# Copy_of_Gandhvedh_U_K.net
KiCad netlist of a schematic drawn in Altium Designer
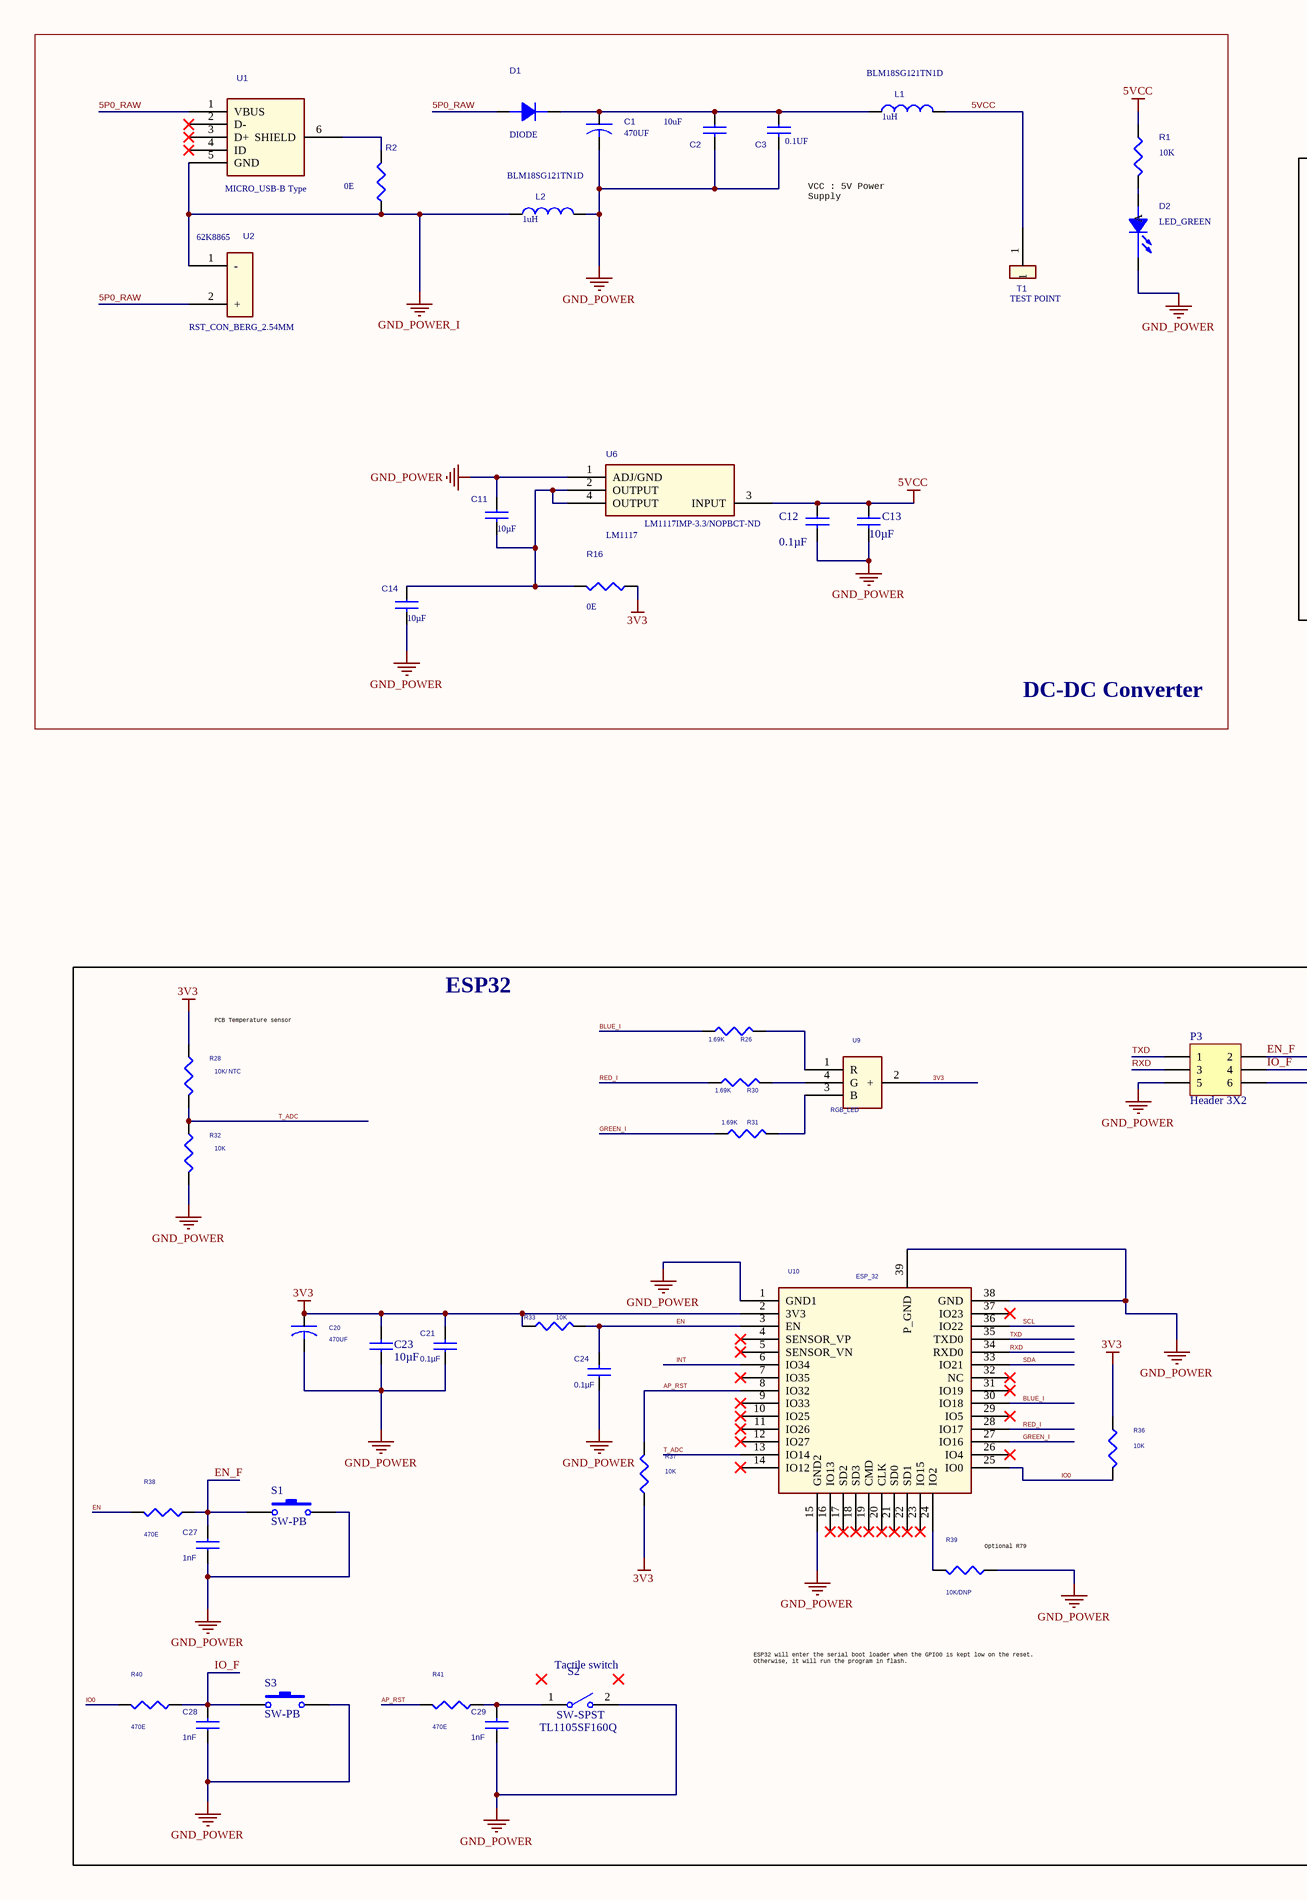
[diagram p0: Copy of Gandhvedh.U.K.SchDoc, left]
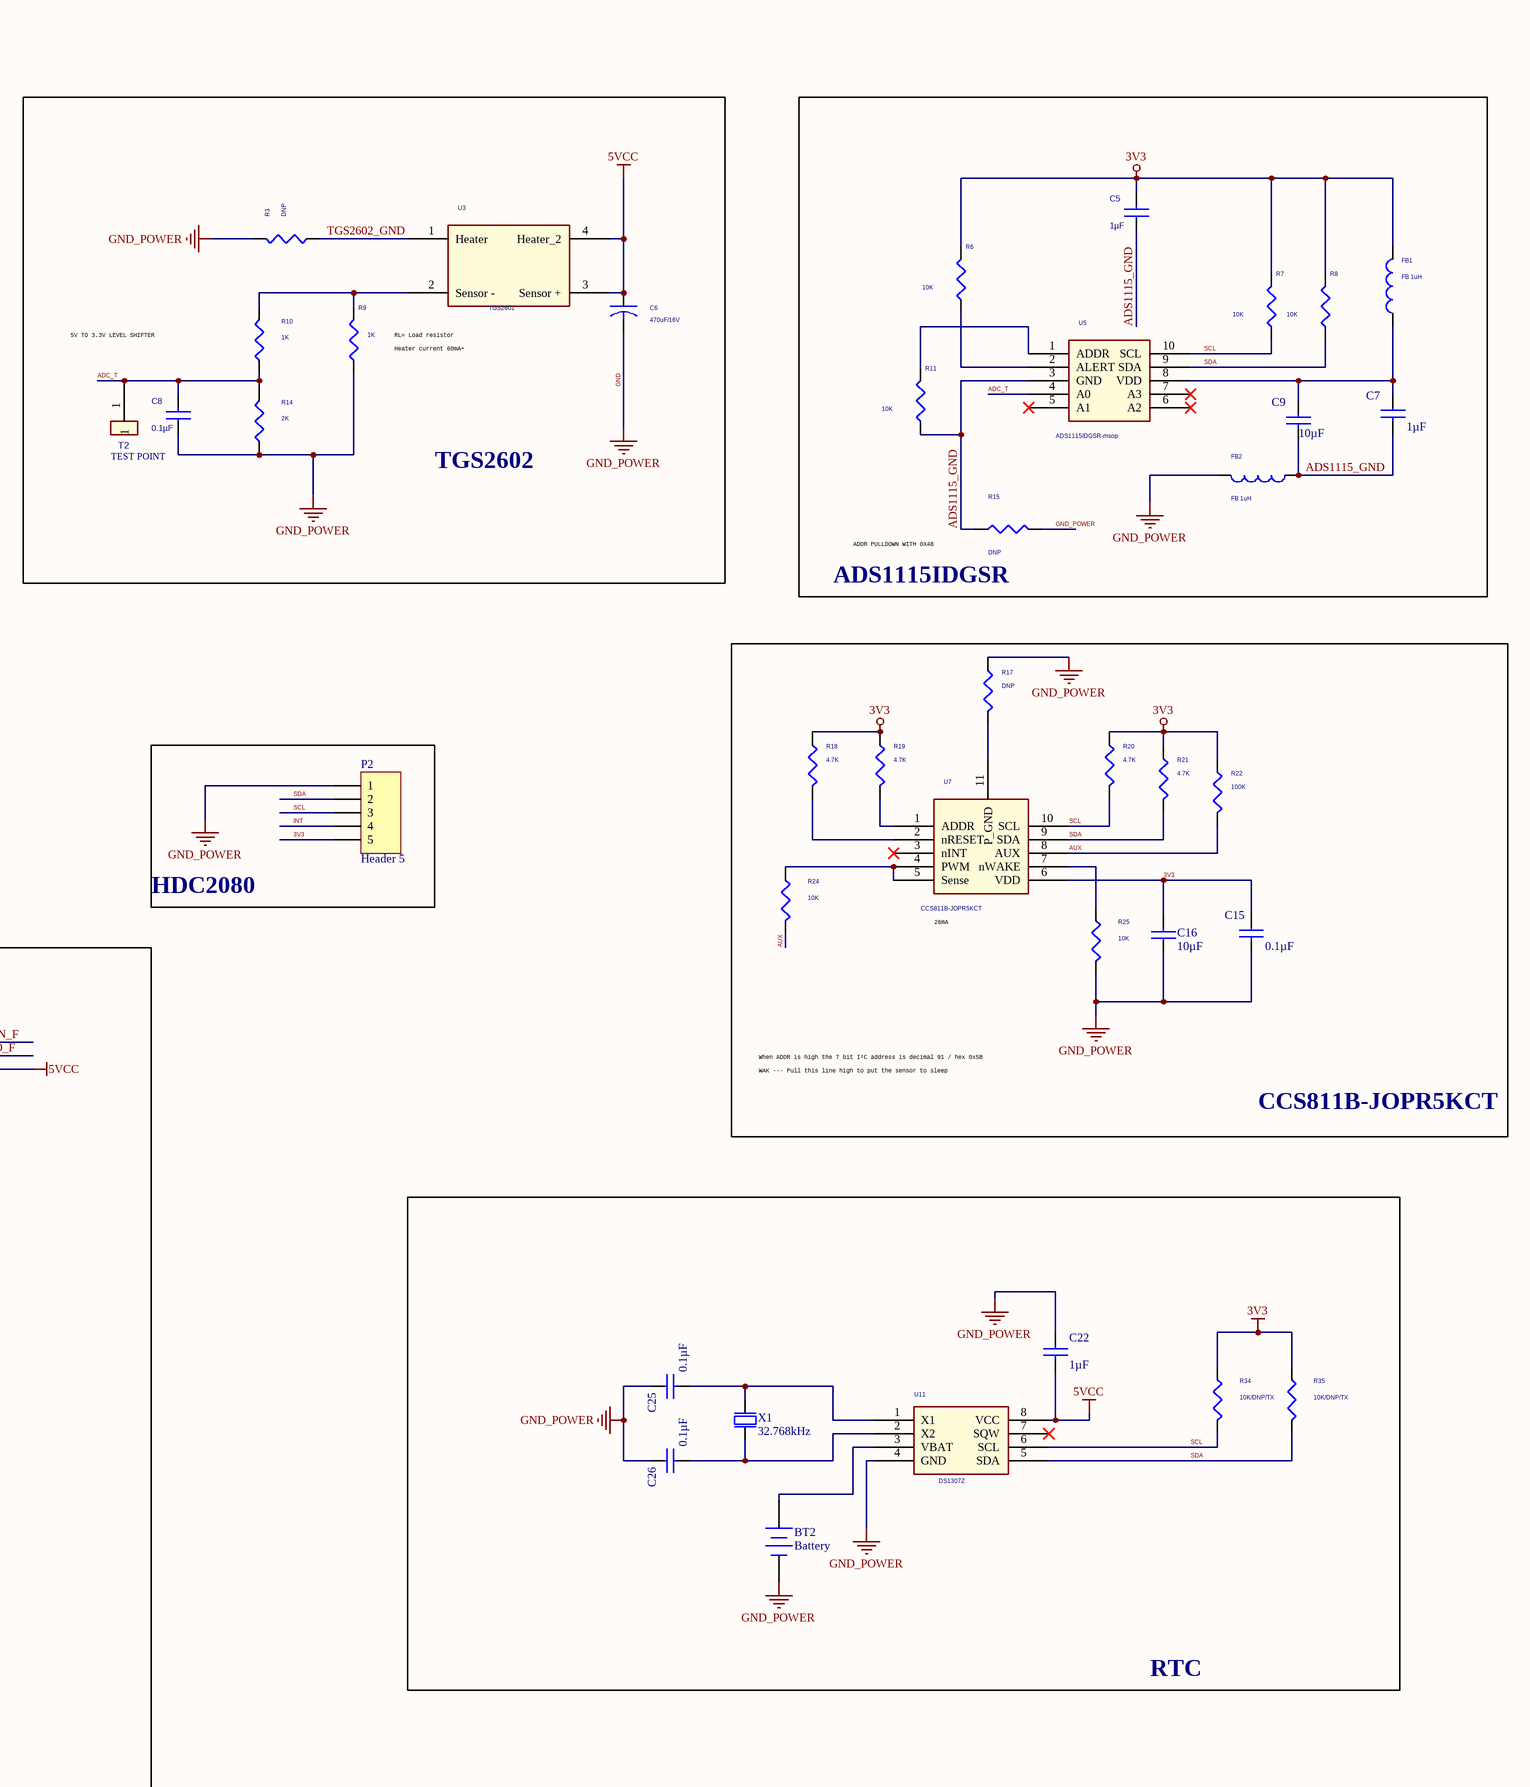
[diagram p1: Copy of Gandhvedh.U.K.SchDoc, middle]
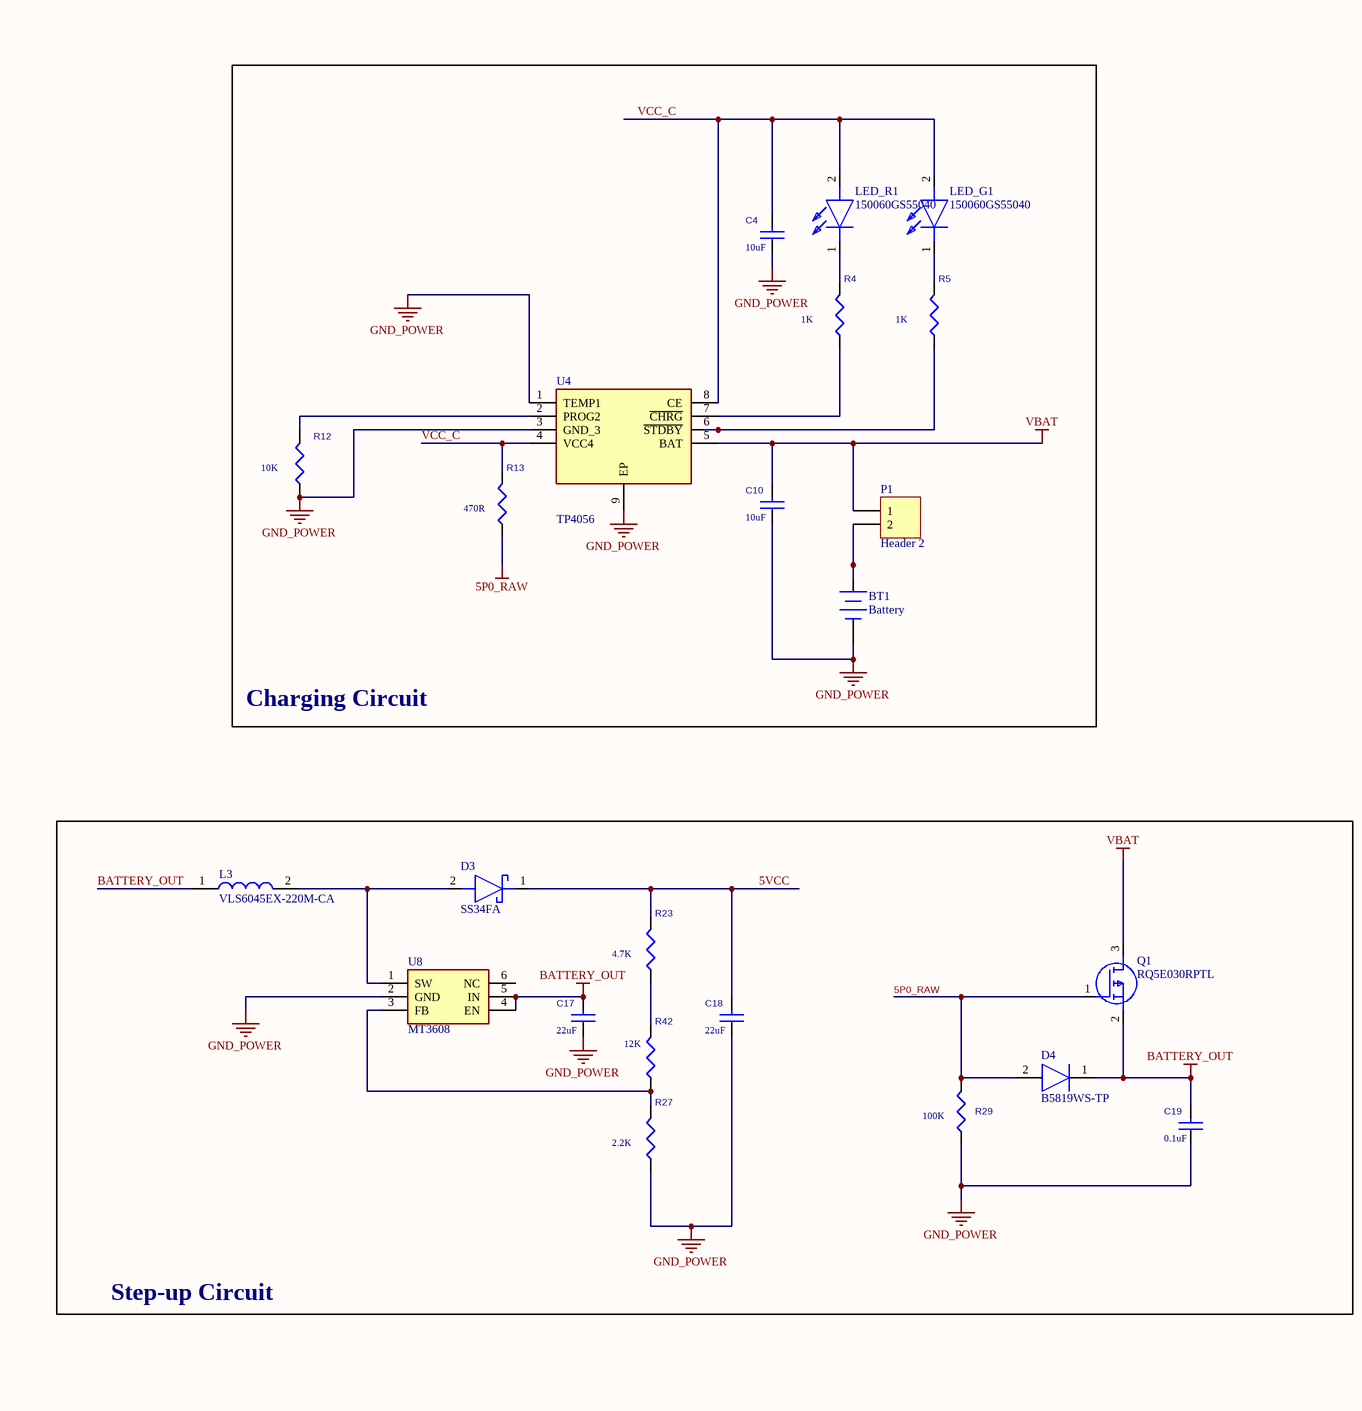
[diagram p2: Copy of Gandhvedh.U.K.SchDoc, right]

(export (version "E")
  (design (tool "Eeschema 10.0.6"))
  (components
    (comp (ref "BT1")
      (value "Battery")
      (footprint "BAT-2")
      (description "Multicell Battery")
      (fields (field (name "PUBLISHER") "Altium Limited"))
      (libsource (lib "Miscellaneous Devices") (part "Battery"))
    )
    (comp (ref "BT2")
      (value "Battery")
      (footprint "Sensor Card:MPD_BK-912-TR")
      (description "Multicell Battery")
      (fields (field (name "PUBLISHER") "Altium Limited"))
      (libsource (lib "Miscellaneous Devices") (part "Battery"))
    )
    (comp (ref "C1")
      (value "470UF")
      (footprint "C16, C49, C58")
      (description "CAP ALUM 470UF 20% 50V RADIAL")
      (fields (field (name "PART NUMBER") "871-B41896E6477M000"))
      (libsource (lib "*") (part "CAP"))
    )
    (comp (ref "C2")
      (value "10uF")
      (footprint "C0603")
      (description "CAP CER 22UF 10V X5R 0603")
      (fields (field (name "PART NUMBER") "GRM188R61A226ME15D"))
      (libsource (lib "*") (part "CAP NP"))
    )
    (comp (ref "C3")
      (value "0.1UF")
      (footprint "C0603")
      (description "CAP CER 22UF 10V X5R 0603")
      (fields (field (name "PART NUMBER") "GRM188R61A226ME15D"))
      (libsource (lib "*") (part "CAP NP"))
    )
    (comp (ref "C4")
      (value "10uF")
      (footprint "PCB1:C0603")
      (description "CAP CER SMD 0.1µF/16V")
      (fields
        (field (name "MANUFACTURER") "Murata Electronics North America")
        (field (name "MANUFACTURER PART NUMBER") "GRM155R61H104KE19D")
      )
      (libsource (lib "Passive Component") (part "CAP_C_0.1µF/16V"))
    )
    (comp (ref "C5")
      (value "1µF")
      (footprint "C0603")
      (description "CAP CER SMD 0.1µF/16V")
      (fields
        (field (name "MANUFACTURER") "Murata Electronics North America")
        (field (name "MANUFACTURER PART NUMBER") "GRM155R61H104KE19D")
      )
      (libsource (lib "Passive Component") (part "CAP_C_0.1µF/16V"))
    )
    (comp (ref "C6")
      (value "470uF/16V")
      (footprint "C16, C49, C58")
      (description "CAP ALUM 470UF 20% 50V RADIAL")
      (fields (field (name "PART NUMBER") "871-B41896E6477M000"))
      (libsource (lib "*") (part "CAP"))
    )
    (comp (ref "C7")
      (value "1µF")
      (footprint "C0603")
      (description "CAP CER SMD 0.1µF/50V")
      (fields
        (field (name "MANUFACTURER") "Yageo")
        (field (name "MANUFACTURER PART NUMBER") "CC0805ZRY5V9BB104")
      )
      (libsource (lib "Passive Component") (part "CAP_C_0.1µF/50V"))
    )
    (comp (ref "C8")
      (value "0.1µF")
      (footprint "C0603")
      (description "CAP CER SMD 0.1µF/16V")
      (fields
        (field (name "MANUFACTURER") "Murata Electronics North America")
        (field (name "MANUFACTURER PART NUMBER") "GRM155R61H104KE19D")
      )
      (libsource (lib "Passive Component") (part "CAP_C_0.1µF/16V"))
    )
    (comp (ref "C9")
      (value "10µF")
      (footprint "C0603")
      (description "CAP CER SMD 10µF/35V")
      (fields
        (field (name "MANUFACTURER") "Taiyo Yuden")
        (field (name "MANUFACTURER PART NUMBER") "GMK316AB7106KL-TR")
      )
      (libsource (lib "Passive Component") (part "CAP_C_10µF/35V"))
    )
    (comp (ref "C10")
      (value "10uF")
      (footprint "PCB1:C0603")
      (description "CAP CER SMD 0.1µF/16V")
      (fields
        (field (name "MANUFACTURER") "Murata Electronics North America")
        (field (name "MANUFACTURER PART NUMBER") "GRM155R61H104KE19D")
      )
      (libsource (lib "Passive Component") (part "CAP_C_0.1µF/16V"))
    )
    (comp (ref "C11")
      (value "10µF")
      (footprint "C0603")
      (description "CAP CER SMD 10µF/35V")
      (fields
        (field (name "MANUFACTURER") "Taiyo Yuden")
        (field (name "MANUFACTURER PART NUMBER") "GMK316AB7106KL-TR")
      )
      (libsource (lib "Passive Component") (part "CAP_C_10µF/35V"))
    )
    (comp (ref "C12")
      (value "0.1µF")
      (footprint "0603 Capacitor")
      (description "CAP CER SMD 0.1µF/50V")
      (fields
        (field (name "MANUFACTURER") "Yageo")
        (field (name "MANUFACTURER PART NUMBER") "CC0805ZRY5V9BB104")
      )
      (libsource (lib "Passive Component") (part "CAP_C_0.1µF/50V"))
    )
    (comp (ref "C13")
      (value "10µF")
      (footprint "0603 Capacitor")
      (description "CAP CER SMD 10µF/35V")
      (fields
        (field (name "MANUFACTURER") "Taiyo Yuden")
        (field (name "MANUFACTURER PART NUMBER") "GMK316AB7106KL-TR")
      )
      (libsource (lib "Passive Component") (part "CAP_C_10µF/35V"))
    )
    (comp (ref "C14")
      (value "10µF")
      (footprint "C0603")
      (description "CAP CER SMD 10µF/35V")
      (fields
        (field (name "MANUFACTURER") "Taiyo Yuden")
        (field (name "MANUFACTURER PART NUMBER") "GMK316AB7106KL-TR")
      )
      (libsource (lib "Passive Component") (part "CAP_C_10µF/35V"))
    )
    (comp (ref "C15")
      (value "0.1µF")
      (footprint "C0603")
      (description "CAP CER SMD 0.1µF/50V")
      (fields
        (field (name "MANUFACTURER") "Yageo")
        (field (name "MANUFACTURER PART NUMBER") "CC0805ZRY5V9BB104")
      )
      (libsource (lib "Passive Component") (part "CAP_C_0.1µF/50V"))
    )
    (comp (ref "C16")
      (value "10µF")
      (footprint "C0603")
      (description "CAP CER SMD 10µF/10V")
      (fields
        (field (name "MANUFACTURER") "Yageo")
        (field (name "MANUFACTURER PART NUMBER") "CC0805ZKY5V6BB106")
      )
      (libsource (lib "Passive Component") (part "CAP_C_10µF/10V"))
    )
    (comp (ref "C17")
      (value "22uF")
      (footprint "PCB1:C0603")
      (description "CAP CER SMD 0.1µF/16V")
      (fields
        (field (name "MANUFACTURER") "Murata Electronics North America")
        (field (name "MANUFACTURER PART NUMBER") "GRM155R61H104KE19D")
      )
      (libsource (lib "Passive Component") (part "CAP_C_0.1µF/16V"))
    )
    (comp (ref "C18")
      (value "22uF")
      (footprint "PCB1:C0603")
      (description "CAP CER SMD 0.1µF/16V")
      (fields
        (field (name "MANUFACTURER") "Murata Electronics North America")
        (field (name "MANUFACTURER PART NUMBER") "GRM155R61H104KE19D")
      )
      (libsource (lib "Passive Component") (part "CAP_C_0.1µF/16V"))
    )
    (comp (ref "C19")
      (value "0.1uF")
      (footprint "PCB1:C0603")
      (description "CAP CER SMD 0.1µF/16V")
      (fields
        (field (name "MANUFACTURER") "Murata Electronics North America")
        (field (name "MANUFACTURER PART NUMBER") "GRM155R61H104KE19D")
      )
      (libsource (lib "Passive Component") (part "CAP_C_0.1µF/16V"))
    )
    (comp (ref "C20")
      (value "470UF")
      (footprint "C16, C49, C58")
      (description "CAP ALUM 470UF 20% 50V RADIAL")
      (fields (field (name "PART NUMBER") "871-B41896E6477M000"))
      (libsource (lib "*") (part "CAP"))
    )
    (comp (ref "C21")
      (value "0.1µF")
      (footprint "0603 Capacitor")
      (description "CAP CER SMD 0.1µF/16V")
      (fields
        (field (name "MANUFACTURER") "Murata Electronics North America")
        (field (name "MANUFACTURER PART NUMBER") "GRM155R61H104KE19D")
      )
      (libsource (lib "Passive Component") (part "CAP_C_0.1µF/16V"))
    )
    (comp (ref "C22")
      (value "1µF")
      (footprint "C0603")
      (description "CAP CER SMD 0.1µF/50V")
      (fields
        (field (name "MANUFACTURER") "Yageo")
        (field (name "MANUFACTURER PART NUMBER") "CC0805ZRY5V9BB104")
      )
      (libsource (lib "Passive Component") (part "CAP_C_0.1µF/50V"))
    )
    (comp (ref "C23")
      (value "10µF")
      (footprint "C0603")
      (description "CAP CER SMD 10µF/10V")
      (fields
        (field (name "MANUFACTURER") "Yageo")
        (field (name "MANUFACTURER PART NUMBER") "CC0805ZKY5V6BB106")
      )
      (libsource (lib "Passive Component") (part "CAP_C_10µF/10V"))
    )
    (comp (ref "C24")
      (value "0.1µF")
      (footprint "C0603")
      (description "CAP CER SMD 0.1µF/16V")
      (fields
        (field (name "MANUFACTURER") "Murata Electronics North America")
        (field (name "MANUFACTURER PART NUMBER") "GRM155R61H104KE19D")
      )
      (libsource (lib "Passive Component") (part "CAP_C_0.1µF/16V"))
    )
    (comp (ref "C25")
      (value "0.1µF")
      (footprint "C0603")
      (description "CAP CER SMD 0.1µF/50V")
      (fields
        (field (name "MANUFACTURER") "Yageo")
        (field (name "MANUFACTURER PART NUMBER") "CC0805ZRY5V9BB104")
      )
      (libsource (lib "Passive Component") (part "CAP_C_0.1µF/50V"))
    )
    (comp (ref "C26")
      (value "0.1µF")
      (footprint "C0603")
      (description "CAP CER SMD 0.1µF/50V")
      (fields
        (field (name "MANUFACTURER") "Yageo")
        (field (name "MANUFACTURER PART NUMBER") "CC0805ZRY5V9BB104")
      )
      (libsource (lib "Passive Component") (part "CAP_C_0.1µF/50V"))
    )
    (comp (ref "C27")
      (value "1nF")
      (footprint "C0603")
      (description "CAP CER SMD 0.1µF/16V")
      (fields
        (field (name "MANUFACTURER") "Murata Electronics North America")
        (field (name "MANUFACTURER PART NUMBER") "GRM155R61H104KE19D")
      )
      (libsource (lib "Passive Component") (part "CAP_C_0.1µF/16V"))
    )
    (comp (ref "C28")
      (value "1nF")
      (footprint "C0603")
      (description "CAP CER SMD 0.1µF/16V")
      (fields
        (field (name "MANUFACTURER") "Murata Electronics North America")
        (field (name "MANUFACTURER PART NUMBER") "GRM155R61H104KE19D")
      )
      (libsource (lib "Passive Component") (part "CAP_C_0.1µF/16V"))
    )
    (comp (ref "C29")
      (value "1nF")
      (footprint "C0603")
      (description "CAP CER SMD 0.1µF/16V")
      (fields
        (field (name "MANUFACTURER") "Murata Electronics North America")
        (field (name "MANUFACTURER PART NUMBER") "GRM155R61H104KE19D")
      )
      (libsource (lib "Passive Component") (part "CAP_C_0.1µF/16V"))
    )
    (comp (ref "D1")
      (value "DIODE")
      (footprint "D1")
      (description "DIODE GEN PURP 1KV 1A DO214AC")
      (fields (field (name "PART NUMBER") "641-1018-2-ND"))
      (libsource (lib "*") (part "DIODE"))
    )
    (comp (ref "D2")
      (value "LED_GREEN")
      (footprint "D2              L0603")
      (description "LED GREEN CLEAR THIN 0603 SMD")
      (fields
        (field (name "DISTRIBUTOR PART NUMBER") "160-1443-1-ND")
        (field (name "MANUFACTURER PART NUMBER") "160-1443-2-ND")
      )
      (libsource (lib "*") (part "LED"))
    )
    (comp (ref "D3")
      (value "SS34FA")
      (footprint "PCB1:D1")
      (description "Schottky Diode")
      (fields (field (name "MOUSER PART NUMBER") "512-SS34FA"))
      (libsource (lib "*") (part "SS34FA"))
    )
    (comp (ref "D4")
      (value "B5819WS-TP")
      (footprint "PCB1:D1")
      (description "Diode")
      (fields (field (name "MOUSER PART NUMBER") "833-B5819WS-TP"))
      (libsource (lib "*") (part "B5819WS-TP"))
    )
    (comp (ref "FB1")
      (value "FB 1uH")
      (footprint "0603 Capacitor")
      (description "FILTER CHIP 120 OHM 3A 0603")
      (fields (field (name "MANUFACTURER PART NUMBER") "MMZ2012Y152B"))
      (libsource (lib "*") (part "INDUCTOR"))
    )
    (comp (ref "FB2")
      (value "FB 1uH")
      (footprint "0603 Capacitor")
      (description "FILTER CHIP 120 OHM 3A 0603")
      (fields (field (name "DISTRIBUTOR PART NUMBER") "MMZ2012Y152B"))
      (libsource (lib "*") (part "INDUCTOR"))
    )
    (comp (ref "L1")
      (value "1uH")
      (footprint "L3, L4, L5, L6, L7")
      (description "FERRITE BEAD 120 OHM 0603 1LN")
      (fields
        (field (name "PART NUMBER") "490-3996-1-ND")
        (field (name "SUPPLIER PART NUMBER 1") "BLM18SG121TN1D")
      )
      (libsource (lib "*") (part "INDUCTOR"))
    )
    (comp (ref "L2")
      (value "1uH")
      (footprint "L3, L4, L5, L6, L7")
      (description "FERRITE BEAD 120 OHM 0603 1LN")
      (fields
        (field (name "PART NUMBER") "490-3996-1-ND")
        (field (name "SUPPLIER PART NUMBER 1") "BLM18SG121TN1D")
      )
      (libsource (lib "*") (part "INDUCTOR"))
    )
    (comp (ref "L3")
      (value "VLS6045EX-220M-CA")
      (footprint "SamacSys:VLS6045")
      (description "Inductor")
      (fields (field (name "MOUSER PART NUMBER") "810-VLS6045EX220MCA"))
      (libsource (lib "*") (part "VLS6045EX-220M-CA"))
    )
    (comp (ref "LED_G1")
      (value "150060GS55040")
      (footprint "SamacSys:LEDC1608X50N")
      (description "LED")
      (fields (field (name "MOUSER PART NUMBER") "710-150060GS55040"))
      (libsource (lib "*") (part "150060GS55040"))
    )
    (comp (ref "LED_R1")
      (value "150060GS55040")
      (footprint "SamacSys:LEDC1608X50N")
      (description "LED")
      (fields (field (name "MOUSER PART NUMBER") "710-150060GS55040"))
      (libsource (lib "*") (part "150060GS55040"))
    )
    (comp (ref "P1")
      (value "Header 2")
      (footprint "Miscellaneous Connectors:HDR1X2")
      (description "Header, 2-Pin")
      (fields (field (name "PUBLISHER") "Altium Limited"))
      (libsource (lib "Miscellaneous Connectors") (part "Header 2"))
    )
    (comp (ref "P2")
      (value "Header 5")
      (footprint "HDR1X5")
      (description "Header, 5-Pin")
      (fields (field (name "PUBLISHER") "Altium Limited"))
      (libsource (lib "Miscellaneous Connectors") (part "Header 5"))
    )
    (comp (ref "P3")
      (value "Header 3X2")
      (footprint "HDR2X3")
      (description "Header, 3-Pin, Dual row")
      (fields (field (name "PUBLISHER") "Altium Limited"))
      (libsource (lib "Miscellaneous Connectors") (part "Header 3X2"))
    )
    (comp (ref "Q1")
      (value "RQ5E030RPTL")
      (footprint "SamacSys:SOT95P280X100-3N")
      (description "MOSFET (P-Channel)")
      (fields (field (name "MOUSER PART NUMBER") "755-RQ5E030RPTL"))
      (libsource (lib "*") (part "RQ5E030RPTL"))
    )
    (comp (ref "R1")
      (value "10K")
      (footprint "R0603")
      (description "RES SMD 1K OHM 5% 1/10W 0603")
      (fields (field (name "PART NUMBER") "311-1.0KGRTR-ND"))
      (libsource (lib "*") (part "R"))
    )
    (comp (ref "R2")
      (value "0E")
      (footprint "R0603")
      (description "RES SMD 4.7K OHM 1% 1/16W 0603")
      (fields (field (name "TOLERANCE") "1%") (field (name "DISTRIBUTOR PART NUMBER") "1276-3466-2-ND"))
      (libsource (lib "*") (part "R"))
    )
    (comp (ref "R3") (value "DNP") (footprint "R0603") (libsource (lib "*") (part "R")))
    (comp (ref "R4")
      (value "1K")
      (footprint "PCB1:R0603")
      (description "RES SMD 4.7K OHM 1% 1/16W 0603")
      (fields (field (name "TOLERANCE") "1%") (field (name "DISTRIBUTOR PART NUMBER") "1276-3466-2-ND"))
      (libsource (lib "*") (part "R"))
    )
    (comp (ref "R5")
      (value "1K")
      (footprint "PCB1:R0603")
      (description "RES SMD 4.7K OHM 1% 1/16W 0603")
      (fields (field (name "TOLERANCE") "1%") (field (name "DISTRIBUTOR PART NUMBER") "1276-3466-2-ND"))
      (libsource (lib "*") (part "R"))
    )
    (comp (ref "R6")
      (value "10K")
      (footprint "R0603")
      (description "RES SMD 4.7K OHM 1% 1/16W 0603")
      (fields (field (name "TOLERANCE") "1%") (field (name "DISTRIBUTOR PART NUMBER") "1276-3466-2-ND"))
      (libsource (lib "*") (part "R"))
    )
    (comp (ref "R7")
      (value "10K")
      (footprint "R0603")
      (description "RES SMD 4.7K OHM 1% 1/16W 0603")
      (fields (field (name "TOLERANCE") "1%") (field (name "DISTRIBUTOR PART NUMBER") "1276-3466-2-ND"))
      (libsource (lib "*") (part "R"))
    )
    (comp (ref "R8")
      (value "10K")
      (footprint "R0603")
      (description "RES SMD 4.7K OHM 1% 1/16W 0603")
      (fields (field (name "TOLERANCE") "1%") (field (name "DISTRIBUTOR PART NUMBER") "1276-3466-2-ND"))
      (libsource (lib "*") (part "R"))
    )
    (comp (ref "R9")
      (value "1K")
      (footprint "R0603")
      (description "RES SMD 1K OHM 5% 1/10W 0603")
      (fields (field (name "PART NUMBER") "311-1.0KGRTR-ND") (field (name "TOLERANCE") "1%"))
      (libsource (lib "*") (part "R"))
    )
    (comp (ref "R10")
      (value "1K")
      (footprint "R0603")
      (description "RES SMD 1K OHM 5% 1/10W 0603")
      (fields (field (name "PART NUMBER") "311-1.0KGRTR-ND"))
      (libsource (lib "*") (part "R"))
    )
    (comp (ref "R11")
      (value "10K")
      (footprint "R0603")
      (description "RES SMD 4.7K OHM 1% 1/16W 0603")
      (fields (field (name "TOLERANCE") "1%") (field (name "DISTRIBUTOR PART NUMBER") "1276-3466-2-ND"))
      (libsource (lib "*") (part "R"))
    )
    (comp (ref "R12")
      (value "10K")
      (footprint "PCB1:R0603")
      (description "RES SMD 4.7K OHM 1% 1/16W 0603")
      (fields (field (name "TOLERANCE") "1%") (field (name "DISTRIBUTOR PART NUMBER") "1276-3466-2-ND"))
      (libsource (lib "*") (part "R"))
    )
    (comp (ref "R13")
      (value "470R")
      (footprint "PCB1:R0603")
      (description "RES SMD 4.7K OHM 1% 1/16W 0603")
      (fields (field (name "TOLERANCE") "1%") (field (name "DISTRIBUTOR PART NUMBER") "1276-3466-2-ND"))
      (libsource (lib "*") (part "R"))
    )
    (comp (ref "R14")
      (value "2K")
      (footprint "R0603")
      (description "RES SMD 2K OHM 1% 1/10W 0603")
      (fields (field (name "PART NUMBER") "YAG1297CT-ND"))
      (libsource (lib "*") (part "R"))
    )
    (comp (ref "R15") (value "DNP") (footprint "R0603") (libsource (lib "*") (part "R")))
    (comp (ref "R16")
      (value "0E")
      (footprint "R0603")
      (description "RES SMD 470 OHM 1% 1/10W 0603")
      (fields (field (name "PART NUMBER") "311-470HRCT-ND"))
      (libsource (lib "*") (part "R"))
    )
    (comp (ref "R17") (value "DNP") (footprint "R0603") (libsource (lib "*") (part "R")))
    (comp (ref "R18")
      (value "4.7K")
      (footprint "R0603")
      (description "P4.7KDBTR-ND")
      (fields (field (name "PART NUMBER") "P4.7KDBDKR-ND"))
      (libsource (lib "*") (part "R"))
    )
    (comp (ref "R19")
      (value "4.7K")
      (footprint "R0603")
      (description "P4.7KDBTR-ND")
      (fields (field (name "PART NUMBER") "P4.7KDBDKR-ND"))
      (libsource (lib "*") (part "R"))
    )
    (comp (ref "R20")
      (value "4.7K")
      (footprint "R0603")
      (description "P4.7KDBTR-ND")
      (fields (field (name "PART NUMBER") "P4.7KDBDKR-ND"))
      (libsource (lib "*") (part "R"))
    )
    (comp (ref "R21")
      (value "4.7K")
      (footprint "R0603")
      (description "P4.7KDBTR-ND")
      (fields (field (name "PART NUMBER") "P4.7KDBDKR-ND"))
      (libsource (lib "*") (part "R"))
    )
    (comp (ref "R22")
      (value "100K")
      (footprint "R0603")
      (description "RES SMD 100K OHM 0.1% 1/10W 0603")
      (fields (field (name "PART NUMBER") "YAG1235TR-ND"))
      (libsource (lib "*") (part "R"))
    )
    (comp (ref "R23")
      (value "4.7K")
      (footprint "PCB1:R0603")
      (description "RES SMD 4.7K OHM 1% 1/16W 0603")
      (fields (field (name "TOLERANCE") "1%") (field (name "DISTRIBUTOR PART NUMBER") "1276-3466-2-ND"))
      (libsource (lib "*") (part "R"))
    )
    (comp (ref "R24")
      (value "10K")
      (footprint "R0603")
      (fields (field (name "PART NUMBER") "594-NTCS402E3103JL1T"))
      (libsource (lib "*") (part "R"))
    )
    (comp (ref "R25")
      (value "10K")
      (footprint "R0603")
      (description "RES SMD 4.7K OHM 1% 1/16W 0603")
      (fields (field (name "PART NUMBER") "311-10KGRTR-ND"))
      (libsource (lib "*") (part "R"))
    )
    (comp (ref "R26")
      (value "1.69K")
      (footprint "R0603")
      (description "RES SMD 4.7K OHM 1% 1/16W 0603")
      (fields (field (name "PART NUMBER") "311-10KGRTR-ND"))
      (libsource (lib "*") (part "R"))
    )
    (comp (ref "R27")
      (value "2.2K")
      (footprint "PCB1:R0603")
      (description "RES SMD 4.7K OHM 1% 1/16W 0603")
      (fields (field (name "TOLERANCE") "1%") (field (name "DISTRIBUTOR PART NUMBER") "1276-3466-2-ND"))
      (libsource (lib "*") (part "R"))
    )
    (comp (ref "R28")
      (value "10K/ NTC")
      (footprint "R0603")
      (description "THERMISTOR NTC 10KOHM 3380K 0603")
      (fields (field (name "PART NUMBER") "490-16279-2-ND"))
      (libsource (lib "*") (part "R"))
    )
    (comp (ref "R29")
      (value "100K")
      (footprint "PCB1:R0603")
      (description "RES SMD 4.7K OHM 1% 1/16W 0603")
      (fields (field (name "TOLERANCE") "1%") (field (name "DISTRIBUTOR PART NUMBER") "1276-3466-2-ND"))
      (libsource (lib "*") (part "R"))
    )
    (comp (ref "R30")
      (value "1.69K")
      (footprint "R0603")
      (description "RES SMD 4.7K OHM 1% 1/16W 0603")
      (fields (field (name "PART NUMBER") "311-10KGRTR-ND"))
      (libsource (lib "*") (part "R"))
    )
    (comp (ref "R31")
      (value "1.69K")
      (footprint "R0603")
      (description "RES SMD 4.7K OHM 1% 1/16W 0603")
      (fields (field (name "PART NUMBER") "311-10KGRTR-ND"))
      (libsource (lib "*") (part "R"))
    )
    (comp (ref "R32")
      (value "10K")
      (footprint "R0603")
      (description "RES SMD 4.7K OHM 1% 1/16W 0603")
      (fields (field (name "PART NUMBER") "311-10KGRTR-ND"))
      (libsource (lib "*") (part "R"))
    )
    (comp (ref "R33")
      (value "10K")
      (footprint "R_0603_W")
      (description "RES SMD 4.7K OHM 1% 1/16W 0603")
      (fields (field (name "PART NUMBER") "311-10KGRTR-ND"))
      (libsource (lib "*") (part "R"))
    )
    (comp (ref "R34")
      (value "10K/DNP/TX")
      (footprint "R0603")
      (description "RES SMD 4.7K OHM 1% 1/16W 0603")
      (fields (field (name "PART NUMBER") "311-10KGRTR-ND"))
      (libsource (lib "*") (part "R"))
    )
    (comp (ref "R35")
      (value "10K/DNP/TX")
      (footprint "R0603")
      (description "RES SMD 4.7K OHM 1% 1/16W 0603")
      (fields (field (name "PART NUMBER") "311-10KGRTR-ND"))
      (libsource (lib "*") (part "R"))
    )
    (comp (ref "R36")
      (value "10K")
      (footprint "R0603")
      (description "RES SMD 4.7K OHM 1% 1/16W 0603")
      (fields (field (name "PART NUMBER") "311-10KGRTR-ND"))
      (libsource (lib "*") (part "R"))
    )
    (comp (ref "R37")
      (value "10K")
      (footprint "R0603")
      (description "RES SMD 4.7K OHM 1% 1/16W 0603")
      (fields (field (name "PART NUMBER") "311-10KGRTR-ND"))
      (libsource (lib "*") (part "R"))
    )
    (comp (ref "R38")
      (value "470E")
      (footprint "R0603")
      (description "RES SMD 470 OHM 1% 1/10W 0603")
      (fields (field (name "PART NUMBER") "311-470HRCT-ND"))
      (libsource (lib "*") (part "R"))
    )
    (comp (ref "R39")
      (value "10K/DNP")
      (footprint "R0603")
      (description "RES SMD 4.7K OHM 1% 1/16W 0603")
      (fields (field (name "PART NUMBER") "311-10KGRTR-ND"))
      (libsource (lib "*") (part "R"))
    )
    (comp (ref "R40")
      (value "470E")
      (footprint "R0603")
      (description "RES SMD 470 OHM 1% 1/10W 0603")
      (fields (field (name "PART NUMBER") "311-470HRCT-ND"))
      (libsource (lib "*") (part "R"))
    )
    (comp (ref "R41")
      (value "470E")
      (footprint "R0603")
      (description "RES SMD 470 OHM 1% 1/10W 0603")
      (fields (field (name "PART NUMBER") "311-470HRCT-ND"))
      (libsource (lib "*") (part "R"))
    )
    (comp (ref "R42")
      (value "12K")
      (footprint "PCB1:R0603")
      (description "RES SMD 4.7K OHM 1% 1/16W 0603")
      (fields (field (name "TOLERANCE") "1%") (field (name "DISTRIBUTOR PART NUMBER") "1276-3466-2-ND"))
      (libsource (lib "*") (part "R"))
    )
    (comp (ref "S1")
      (value "SW-PB")
      (footprint "S2, S3")
      (description "Switch")
      (fields (field (name "PUBLISHER") "Altium Limited"))
      (libsource (lib "Miscellaneous Devices") (part "SW-PB"))
    )
    (comp (ref "S2")
      (value "SW-SPST")
      (footprint "S1")
      (description "SWITCH TACTILE SPST-NO 0.05A 12V")
      (fields (field (name "PART NUMBER") "TL1105SF160Q") (field (name "PUBLISHER") "Altium Limited"))
      (libsource (lib "Miscellaneous Devices") (part "SW-SPST"))
    )
    (comp (ref "S3")
      (value "SW-PB")
      (footprint "S2, S3")
      (description "Switch")
      (fields (field (name "PUBLISHER") "Altium Limited"))
      (libsource (lib "Miscellaneous Devices") (part "SW-PB"))
    )
    (comp (ref "T1") (value "TEST POINT") (footprint "TP") (libsource (lib "*") (part "Test_P")))
    (comp (ref "T2") (value "TEST POINT") (footprint "TP") (libsource (lib "*") (part "Test_P")))
    (comp (ref "U1")
      (value "MICRO_USB-B Type")
      (footprint "U22")
      (description "CONN RCPT USB2.0 MICRO B SMD R/A")
      (libsource (lib "*") (part "MIcro_USB"))
    )
    (comp (ref "U2")
      (value "RST_CON_BERG_2.54MM")
      (footprint "U23")
      (description "CONN HEADER VERT 2POS 2.54MM")
      (fields (field (name "PART NUMBER") "609-4434-ND") (field (name "SUPPLIER PART NUMBER 1") "62K8865"))
      (libsource (lib "*") (part "CON_AC_1"))
    )
    (comp (ref "U3") (value "TGS2602") (footprint "TGS2602") (libsource (lib "*") (part "TGS2602_1")))
    (comp (ref "U4")
      (value "TP4056")
      (footprint "SamacSys:SOIC127P600X175-9N")
      (description "Connector")
      (libsource (lib "*") (part "TP4056"))
    )
    (comp (ref "U5")
      (value "ADS1115IDGSR-msop")
      (footprint "U19, U20")
      (description "IC ADC 16BIT SIGMA-DELTA 10VSSOP")
      (fields (field (name "PART NUMBER") "595-ADS1115IDGST"))
      (libsource (lib "*") (part "ADS1115"))
    )
    (comp (ref "U6")
      (value "LM1117")
      (footprint "U1, U24              SOT-223")
      (description "3.3V LDO")
      (fields
        (field (name "MANUFACTURER") "Texas Instruments")
        (field (name "SUPPLIER PART NUMBER 1") "LM1117IMP-3.3/NOPBCT-ND")
      )
      (libsource (lib "PMIC") (part "TLV70033DDCT"))
    )
    (comp (ref "U7")
      (value "CCS811B-JOPR5KCT")
      (footprint "*SON60P400X270X110-11N")
      (description "CCS811B-JOPR5K LGA10 LF T&R")
      (fields (field (name "PART NUMBER") "CCS811B-JOPR5KCT-ND"))
      (libsource (lib "*") (part "CCS811B-JOPR5KCT_3"))
    )
    (comp (ref "U8")
      (value "MT3608")
      (footprint "SamacSys:SOT95P280X145-6N")
      (description "Undefined or Miscellaneous")
      (libsource (lib "*") (part "MT3608"))
    )
    (comp (ref "U9")
      (value "RGB_LED")
      (footprint "Sensor Card:WL-SFCW_1206")
      (fields (field (name "PART NUMBER") "754-1492-ND"))
      (libsource (lib "*") (part "RGB_LED_PTH_0"))
    )
    (comp (ref "U10")
      (value "ESP_32")
      (footprint "U20             ESP 32")
      (description "WIFI MODULE 128MBITS SPI FLASH")
      (fields (field (name "PART NUMBER") "356-ES32WROOM32D16MB"))
      (libsource (lib "*") (part "ESP32_SMD_1"))
    )
    (comp (ref "U11")
      (value "DS1307Z")
      (footprint "U6, U8                    SOIC-8N")
      (description "IC REG BUCK ADJUSTABLE 3A 8SOIC")
      (fields (field (name "PART NUMBER") "1589-1533-1-ND"))
      (libsource (lib "*") (part "MP1584_SOIC_0"))
    )
    (comp (ref "X1")
      (value "32.768kHz")
      (footprint "XTAL")
      (description "XTAL SMD 3215, 32.768kHz, Cl=9pF, Total Tol: ±50ppm")
      (fields
        (field (name "PART NUMBER") "XTAL_SMD3215_32.768kHz_9pF_General")
        (field (name "PUBLISHER") "Nordic Semiconductor")
      )
      (libsource (lib "Sensor Card") (part "XTAL_2-pin"))
    )
  )
  (nets
    (net (code "1") (name "/ADC_T") (class "Default")
      (node (ref "C8") (pin "2") (pinfunction "2_2") (pintype "passive"))
      (node (ref "R10") (pin "1") (pinfunction "1_1") (pintype "passive"))
      (node (ref "R14") (pin "2") (pinfunction "2_2") (pintype "passive"))
      (node (ref "T2") (pin "1") (pinfunction "1_1") (pintype "passive"))
      (node (ref "U5") (pin "4") (pinfunction "A0_4") (pintype "passive"))
    )
    (net (code "2") (name "/ADS1115_GND") (class "Default")
      (node (ref "C5") (pin "1") (pinfunction "1_1") (pintype "passive"))
      (node (ref "C7") (pin "2") (pinfunction "2_2") (pintype "passive"))
      (node (ref "C9") (pin "2") (pinfunction "2_2") (pintype "passive"))
      (node (ref "FB2") (pin "1") (pinfunction "1_1") (pintype "passive"))
      (node (ref "R11") (pin "2") (pinfunction "2_2") (pintype "passive"))
      (node (ref "R15") (pin "1") (pinfunction "1_1") (pintype "passive"))
      (node (ref "U5") (pin "3") (pinfunction "GND_3") (pintype "passive"))
    )
    (net (code "3") (name "/AP_RST") (class "Default")
      (node (ref "R37") (pin "2") (pinfunction "2_2") (pintype "passive"))
      (node (ref "R41") (pin "2") (pinfunction "2_2") (pintype "passive"))
      (node (ref "U10") (pin "8") (pinfunction "IO32_8") (pintype "passive"))
    )
    (net (code "4") (name "/AUX") (class "Default")
      (node (ref "R22") (pin "2") (pinfunction "2_2") (pintype "passive"))
      (node (ref "R24") (pin "2") (pinfunction "2_2") (pintype "passive"))
      (node (ref "U7") (pin "8") (pinfunction "AUX_8") (pintype "passive"))
    )
    (net (code "5") (name "/BLUE_I") (class "Default")
      (node (ref "R26") (pin "1") (pinfunction "1_1") (pintype "passive"))
      (node (ref "U10") (pin "30") (pinfunction "IO18_30") (pintype "passive"))
    )
    (net (code "6") (name "/EN") (class "Default")
      (node (ref "C24") (pin "2") (pinfunction "2_2") (pintype "passive"))
      (node (ref "R33") (pin "2") (pinfunction "2_2") (pintype "passive"))
      (node (ref "R38") (pin "2") (pinfunction "2_2") (pintype "passive"))
      (node (ref "U10") (pin "3") (pinfunction "EN_3") (pintype "passive"))
    )
    (net (code "7") (name "/EN_F") (class "Default")
      (node (ref "C27") (pin "2") (pinfunction "2_2") (pintype "passive"))
      (node (ref "P3") (pin "2") (pinfunction "2_2") (pintype "passive"))
      (node (ref "R38") (pin "1") (pinfunction "1_1") (pintype "passive"))
      (node (ref "S1") (pin "1") (pinfunction "1_1") (pintype "passive"))
    )
    (net (code "8") (name "/GREEN_I") (class "Default")
      (node (ref "R31") (pin "1") (pinfunction "1_1") (pintype "passive"))
      (node (ref "U10") (pin "27") (pinfunction "IO16_27") (pintype "passive"))
    )
    (net (code "9") (name "/INT") (class "Default")
      (node (ref "P2") (pin "4") (pinfunction "4_4") (pintype "passive"))
      (node (ref "U10") (pin "6") (pinfunction "IO34_6") (pintype "passive"))
    )
    (net (code "10") (name "/IO0") (class "Default")
      (node (ref "R36") (pin "2") (pinfunction "2_2") (pintype "passive"))
      (node (ref "R40") (pin "2") (pinfunction "2_2") (pintype "passive"))
      (node (ref "U10") (pin "25") (pinfunction "IO0_25") (pintype "passive"))
    )
    (net (code "11") (name "/IO_F") (class "Default")
      (node (ref "C28") (pin "2") (pinfunction "2_2") (pintype "passive"))
      (node (ref "P3") (pin "4") (pinfunction "4_4") (pintype "passive"))
      (node (ref "R40") (pin "1") (pinfunction "1_1") (pintype "passive"))
      (node (ref "S3") (pin "1") (pinfunction "1_1") (pintype "passive"))
    )
    (net (code "12") (name "/RED_I") (class "Default")
      (node (ref "R30") (pin "1") (pinfunction "1_1") (pintype "passive"))
      (node (ref "U10") (pin "28") (pinfunction "IO17_28") (pintype "passive"))
    )
    (net (code "13") (name "/RXD") (class "Default")
      (node (ref "P3") (pin "3") (pinfunction "3_3") (pintype "passive"))
      (node (ref "U10") (pin "34") (pinfunction "RXD0_34") (pintype "passive"))
    )
    (net (code "14") (name "/SCL") (class "Default")
      (node (ref "P2") (pin "3") (pinfunction "3_3") (pintype "passive"))
      (node (ref "R20") (pin "2") (pinfunction "2_2") (pintype "passive"))
      (node (ref "R34") (pin "2") (pinfunction "2_2") (pintype "passive"))
      (node (ref "R7") (pin "2") (pinfunction "2_2") (pintype "passive"))
      (node (ref "U10") (pin "36") (pinfunction "IO22_36") (pintype "passive"))
      (node (ref "U11") (pin "6") (pinfunction "SCL_6") (pintype "passive"))
      (node (ref "U5") (pin "10") (pinfunction "SCL_10") (pintype "passive"))
      (node (ref "U7") (pin "10") (pinfunction "SCL_10") (pintype "passive"))
    )
    (net (code "15") (name "/SDA") (class "Default")
      (node (ref "P2") (pin "2") (pinfunction "2_2") (pintype "passive"))
      (node (ref "R21") (pin "2") (pinfunction "2_2") (pintype "passive"))
      (node (ref "R35") (pin "2") (pinfunction "2_2") (pintype "passive"))
      (node (ref "R8") (pin "2") (pinfunction "2_2") (pintype "passive"))
      (node (ref "U10") (pin "33") (pinfunction "IO21_33") (pintype "passive"))
      (node (ref "U11") (pin "5") (pinfunction "SDA_5") (pintype "passive"))
      (node (ref "U5") (pin "9") (pinfunction "SDA_9") (pintype "passive"))
      (node (ref "U7") (pin "9") (pinfunction "SDA_9") (pintype "passive"))
    )
    (net (code "16") (name "/TGS2602_GND") (class "Default")
      (node (ref "R3") (pin "1") (pinfunction "1_1") (pintype "passive"))
      (node (ref "U3") (pin "1") (pinfunction "Heater_1") (pintype "passive"))
    )
    (net (code "17") (name "/TXD") (class "Default")
      (node (ref "P3") (pin "1") (pinfunction "1_1") (pintype "passive"))
      (node (ref "U10") (pin "35") (pinfunction "TXD0_35") (pintype "passive"))
    )
    (net (code "18") (name "/T_ADC") (class "Default")
      (node (ref "R28") (pin "2") (pinfunction "2_2") (pintype "passive"))
      (node (ref "R32") (pin "1") (pinfunction "1_1") (pintype "passive"))
      (node (ref "U10") (pin "13") (pinfunction "IO14_13") (pintype "passive"))
    )
    (net (code "19") (name "/VCC_C") (class "Default")
      (node (ref "C4") (pin "2") (pinfunction "2_2") (pintype "passive"))
      (node (ref "LED_G1") (pin "2") (pinfunction "A_2") (pintype "passive"))
      (node (ref "LED_R1") (pin "2") (pinfunction "A_2") (pintype "passive"))
      (node (ref "R13") (pin "1") (pinfunction "1_1") (pintype "passive"))
      (node (ref "U4") (pin "4") (pinfunction "VCC4_4") (pintype "passive"))
      (node (ref "U4") (pin "8") (pinfunction "CE_8") (pintype "passive"))
    )
    (net (code "20") (name "3V3") (class "Default")
      (node (ref "C15") (pin "1") (pinfunction "1_1") (pintype "passive"))
      (node (ref "C16") (pin "2") (pinfunction "2_2") (pintype "passive"))
      (node (ref "C20") (pin "1") (pinfunction "1_1") (pintype "passive"))
      (node (ref "C21") (pin "2") (pinfunction "2_2") (pintype "passive"))
      (node (ref "C23") (pin "2") (pinfunction "2_2") (pintype "passive"))
      (node (ref "C5") (pin "2") (pinfunction "2_2") (pintype "passive"))
      (node (ref "FB1") (pin "2") (pinfunction "2_2") (pintype "passive"))
      (node (ref "P2") (pin "5") (pinfunction "5_5") (pintype "passive"))
      (node (ref "R16") (pin "1") (pinfunction "1_1") (pintype "passive"))
      (node (ref "R18") (pin "1") (pinfunction "1_1") (pintype "passive"))
      (node (ref "R19") (pin "1") (pinfunction "1_1") (pintype "passive"))
      (node (ref "R20") (pin "1") (pinfunction "1_1") (pintype "passive"))
      (node (ref "R21") (pin "1") (pinfunction "1_1") (pintype "passive"))
      (node (ref "R22") (pin "1") (pinfunction "1_1") (pintype "passive"))
      (node (ref "R28") (pin "1") (pinfunction "1_1") (pintype "passive"))
      (node (ref "R33") (pin "1") (pinfunction "1_1") (pintype "passive"))
      (node (ref "R34") (pin "1") (pinfunction "1_1") (pintype "passive"))
      (node (ref "R35") (pin "1") (pinfunction "1_1") (pintype "passive"))
      (node (ref "R36") (pin "1") (pinfunction "1_1") (pintype "passive"))
      (node (ref "R37") (pin "1") (pinfunction "1_1") (pintype "passive"))
      (node (ref "R6") (pin "1") (pinfunction "1_1") (pintype "passive"))
      (node (ref "R7") (pin "1") (pinfunction "1_1") (pintype "passive"))
      (node (ref "R8") (pin "1") (pinfunction "1_1") (pintype "passive"))
      (node (ref "U10") (pin "2") (pinfunction "3V3_2") (pintype "passive"))
      (node (ref "U7") (pin "6") (pinfunction "VDD_6") (pintype "passive"))
      (node (ref "U9") (pin "2") (pinfunction "+_2") (pintype "passive"))
    )
    (net (code "21") (name "5P0_RAW") (class "Default")
      (node (ref "D1") (pin "2") (pinfunction "A_2") (pintype "passive"))
      (node (ref "D4") (pin "2") (pinfunction "A_2") (pintype "passive"))
      (node (ref "Q1") (pin "1") (pinfunction "G_1") (pintype "passive"))
      (node (ref "R13") (pin "2") (pinfunction "2_2") (pintype "passive"))
      (node (ref "R29") (pin "1") (pinfunction "1_1") (pintype "passive"))
      (node (ref "U1") (pin "1") (pinfunction "VBUS_1") (pintype "passive"))
      (node (ref "U2") (pin "2") (pinfunction "+_2") (pintype "passive"))
    )
    (net (code "22") (name "5VCC") (class "Default")
      (node (ref "C12") (pin "1") (pinfunction "1_1") (pintype "passive"))
      (node (ref "C13") (pin "1") (pinfunction "1_1") (pintype "passive"))
      (node (ref "C18") (pin "2") (pinfunction "2_2") (pintype "passive"))
      (node (ref "C22") (pin "2") (pinfunction "2_2") (pintype "passive"))
      (node (ref "C6") (pin "1") (pinfunction "1_1") (pintype "passive"))
      (node (ref "D3") (pin "1") (pinfunction "K_1") (pintype "passive"))
      (node (ref "L1") (pin "2") (pinfunction "2_2") (pintype "passive"))
      (node (ref "P3") (pin "6") (pinfunction "6_6") (pintype "passive"))
      (node (ref "R1") (pin "1") (pinfunction "1_1") (pintype "passive"))
      (node (ref "R23") (pin "1") (pinfunction "1_1") (pintype "passive"))
      (node (ref "T1") (pin "1") (pinfunction "1_1") (pintype "passive"))
      (node (ref "U11") (pin "8") (pinfunction "VCC_8") (pintype "power_in"))
      (node (ref "U3") (pin "3") (pinfunction "Sensor_+_3") (pintype "passive"))
      (node (ref "U3") (pin "4") (pinfunction "Heater_2_4") (pintype "passive"))
      (node (ref "U6") (pin "3") (pinfunction "INPUT_3") (pintype "passive"))
    )
    (net (code "23") (name "BATTERY_OUT") (class "Default")
      (node (ref "C17") (pin "2") (pinfunction "2_2") (pintype "passive"))
      (node (ref "C19") (pin "2") (pinfunction "2_2") (pintype "passive"))
      (node (ref "D4") (pin "1") (pinfunction "K_1") (pintype "passive"))
      (node (ref "L3") (pin "1") (pinfunction "1_1") (pintype "passive"))
      (node (ref "Q1") (pin "2") (pinfunction "S_2") (pintype "passive"))
      (node (ref "U8") (pin "4") (pinfunction "EN_4") (pintype "passive"))
      (node (ref "U8") (pin "5") (pinfunction "IN_5") (pintype "passive"))
    )
    (net (code "24") (name "GND_POWER") (class "Default")
      (node (ref "BT1") (pin "2") (pinfunction "-_2") (pintype "passive"))
      (node (ref "BT2") (pin "2") (pinfunction "-_2") (pintype "passive"))
      (node (ref "C1") (pin "2") (pinfunction "2_2") (pintype "passive"))
      (node (ref "C10") (pin "1") (pinfunction "1_1") (pintype "passive"))
      (node (ref "C11") (pin "1") (pinfunction "1_1") (pintype "passive"))
      (node (ref "C12") (pin "2") (pinfunction "2_2") (pintype "passive"))
      (node (ref "C13") (pin "2") (pinfunction "2_2") (pintype "passive"))
      (node (ref "C14") (pin "2") (pinfunction "2_2") (pintype "passive"))
      (node (ref "C15") (pin "2") (pinfunction "2_2") (pintype "passive"))
      (node (ref "C16") (pin "1") (pinfunction "1_1") (pintype "passive"))
      (node (ref "C17") (pin "1") (pinfunction "1_1") (pintype "passive"))
      (node (ref "C18") (pin "1") (pinfunction "1_1") (pintype "passive"))
      (node (ref "C19") (pin "1") (pinfunction "1_1") (pintype "passive"))
      (node (ref "C2") (pin "2") (pinfunction "2_2") (pintype "passive"))
      (node (ref "C20") (pin "2") (pinfunction "2_2") (pintype "passive"))
      (node (ref "C21") (pin "1") (pinfunction "1_1") (pintype "passive"))
      (node (ref "C22") (pin "1") (pinfunction "1_1") (pintype "passive"))
      (node (ref "C23") (pin "1") (pinfunction "1_1") (pintype "passive"))
      (node (ref "C24") (pin "1") (pinfunction "1_1") (pintype "passive"))
      (node (ref "C25") (pin "1") (pinfunction "1_1") (pintype "passive"))
      (node (ref "C26") (pin "1") (pinfunction "1_1") (pintype "passive"))
      (node (ref "C27") (pin "1") (pinfunction "1_1") (pintype "passive"))
      (node (ref "C28") (pin "1") (pinfunction "1_1") (pintype "passive"))
      (node (ref "C29") (pin "1") (pinfunction "1_1") (pintype "passive"))
      (node (ref "C3") (pin "2") (pinfunction "2_2") (pintype "passive"))
      (node (ref "C4") (pin "1") (pinfunction "1_1") (pintype "passive"))
      (node (ref "C6") (pin "2") (pinfunction "2_2") (pintype "passive"))
      (node (ref "C8") (pin "1") (pinfunction "1_1") (pintype "passive"))
      (node (ref "D2") (pin "2") (pinfunction "CATHODE_2") (pintype "passive"))
      (node (ref "FB2") (pin "2") (pinfunction "2_2") (pintype "passive"))
      (node (ref "L2") (pin "2") (pinfunction "2_2") (pintype "passive"))
      (node (ref "P2") (pin "1") (pinfunction "1_1") (pintype "passive"))
      (node (ref "P3") (pin "5") (pinfunction "5_5") (pintype "passive"))
      (node (ref "R12") (pin "2") (pinfunction "2_2") (pintype "passive"))
      (node (ref "R14") (pin "1") (pinfunction "1_1") (pintype "passive"))
      (node (ref "R15") (pin "2") (pinfunction "2_2") (pintype "passive"))
      (node (ref "R17") (pin "1") (pinfunction "1_1") (pintype "passive"))
      (node (ref "R25") (pin "2") (pinfunction "2_2") (pintype "passive"))
      (node (ref "R27") (pin "2") (pinfunction "2_2") (pintype "passive"))
      (node (ref "R29") (pin "2") (pinfunction "2_2") (pintype "passive"))
      (node (ref "R3") (pin "2") (pinfunction "2_2") (pintype "passive"))
      (node (ref "R32") (pin "2") (pinfunction "2_2") (pintype "passive"))
      (node (ref "R39") (pin "1") (pinfunction "1_1") (pintype "passive"))
      (node (ref "R9") (pin "2") (pinfunction "2_2") (pintype "passive"))
      (node (ref "S1") (pin "2") (pinfunction "2_2") (pintype "passive"))
      (node (ref "S2") (pin "2") (pinfunction "NO_2") (pintype "passive"))
      (node (ref "S3") (pin "2") (pinfunction "2_2") (pintype "passive"))
      (node (ref "U10") (pin "1") (pinfunction "GND1_1") (pintype "passive"))
      (node (ref "U10") (pin "15") (pinfunction "GND2_15") (pintype "passive"))
      (node (ref "U10") (pin "38") (pinfunction "GND_38") (pintype "passive"))
      (node (ref "U10") (pin "39") (pinfunction "P_GND_39") (pintype "passive"))
      (node (ref "U11") (pin "4") (pinfunction "GND_4") (pintype "power_in"))
      (node (ref "U4") (pin "1") (pinfunction "TEMP1_1") (pintype "passive"))
      (node (ref "U4") (pin "3") (pinfunction "GND_3_3") (pintype "passive"))
      (node (ref "U4") (pin "9") (pinfunction "EP_9") (pintype "passive"))
      (node (ref "U6") (pin "1") (pinfunction "ADJ/GND_1") (pintype "passive"))
      (node (ref "U8") (pin "2") (pinfunction "GND_2") (pintype "passive"))
    )
    (net (code "25") (name "GND_POWER_I") (class "Default")
      (node (ref "L2") (pin "1") (pinfunction "1_1") (pintype "passive"))
      (node (ref "R2") (pin "2") (pinfunction "2_2") (pintype "passive"))
      (node (ref "U1") (pin "5") (pinfunction "GND_5") (pintype "passive"))
      (node (ref "U2") (pin "1") (pinfunction "-_1") (pintype "passive"))
    )
    (net (code "26") (name "Net-(BT1-+)") (class "Default")
      (node (ref "BT1") (pin "1") (pinfunction "+_1") (pintype "passive"))
      (node (ref "P1") (pin "2") (pinfunction "2_2") (pintype "passive"))
    )
    (net (code "27") (name "Net-(BT2-+)") (class "Default")
      (node (ref "BT2") (pin "1") (pinfunction "+_1") (pintype "passive"))
      (node (ref "U11") (pin "3") (pinfunction "VBAT_3") (pintype "passive"))
    )
    (net (code "28") (name "Net-(C11-Pad2)") (class "Default")
      (node (ref "C11") (pin "2") (pinfunction "2_2") (pintype "passive"))
      (node (ref "C14") (pin "1") (pinfunction "1_1") (pintype "passive"))
      (node (ref "R16") (pin "2") (pinfunction "2_2") (pintype "passive"))
      (node (ref "U6") (pin "2") (pinfunction "OUTPUT_2") (pintype "passive"))
      (node (ref "U6") (pin "4") (pinfunction "OUTPUT_4") (pintype "passive"))
    )
    (net (code "29") (name "Net-(D1-K)") (class "Default")
      (node (ref "C1") (pin "1") (pinfunction "1_1") (pintype "passive"))
      (node (ref "C2") (pin "1") (pinfunction "1_1") (pintype "passive"))
      (node (ref "C3") (pin "1") (pinfunction "1_1") (pintype "passive"))
      (node (ref "D1") (pin "1") (pinfunction "K_1") (pintype "passive"))
      (node (ref "L1") (pin "1") (pinfunction "1_1") (pintype "passive"))
    )
    (net (code "30") (name "Net-(D2-A)") (class "Default")
      (node (ref "D2") (pin "1") (pinfunction "A_1") (pintype "passive"))
      (node (ref "R1") (pin "2") (pinfunction "2_2") (pintype "passive"))
    )
    (net (code "31") (name "Net-(D3-A)") (class "Default")
      (node (ref "D3") (pin "2") (pinfunction "A_2") (pintype "passive"))
      (node (ref "L3") (pin "2") (pinfunction "2_2") (pintype "passive"))
      (node (ref "U8") (pin "1") (pinfunction "SW_1") (pintype "passive"))
    )
    (net (code "32") (name "Net-(LED_G1-K)") (class "Default")
      (node (ref "LED_G1") (pin "1") (pinfunction "K_1") (pintype "passive"))
      (node (ref "R5") (pin "1") (pinfunction "1_1") (pintype "passive"))
    )
    (net (code "33") (name "Net-(LED_R1-K)") (class "Default")
      (node (ref "LED_R1") (pin "1") (pinfunction "K_1") (pintype "passive"))
      (node (ref "R4") (pin "1") (pinfunction "1_1") (pintype "passive"))
    )
    (net (code "34") (name "Net-(R23-Pad2)") (class "Default")
      (node (ref "R23") (pin "2") (pinfunction "2_2") (pintype "passive"))
      (node (ref "R42") (pin "1") (pinfunction "1_1") (pintype "passive"))
    )
    (net (code "35") (name "Net-(S2-COMMON)") (class "Default")
      (node (ref "C29") (pin "2") (pinfunction "2_2") (pintype "passive"))
      (node (ref "R41") (pin "1") (pinfunction "1_1") (pintype "passive"))
      (node (ref "S2") (pin "1") (pinfunction "COMMON_1") (pintype "passive"))
    )
    (net (code "36") (name "Net-(U1-SHIELD)") (class "Default")
      (node (ref "R2") (pin "1") (pinfunction "1_1") (pintype "passive"))
      (node (ref "U1") (pin "6") (pinfunction "SHIELD_6") (pintype "passive"))
    )
    (net (code "37") (name "Net-(U3-Sensor_-)") (class "Default")
      (node (ref "R10") (pin "2") (pinfunction "2_2") (pintype "passive"))
      (node (ref "R9") (pin "1") (pinfunction "1_1") (pintype "passive"))
      (node (ref "U3") (pin "2") (pinfunction "Sensor_-_2") (pintype "passive"))
    )
    (net (code "38") (name "Net-(U4-PROG2)") (class "Default")
      (node (ref "R12") (pin "1") (pinfunction "1_1") (pintype "passive"))
      (node (ref "U4") (pin "2") (pinfunction "PROG2_2") (pintype "passive"))
    )
    (net (code "39") (name "Net-(U4-~{CHRG})") (class "Default")
      (node (ref "R4") (pin "2") (pinfunction "2_2") (pintype "passive"))
      (node (ref "U4") (pin "7") (pinfunction "~{CHRG}_7") (pintype "passive"))
    )
    (net (code "40") (name "Net-(U4-~{STDBY})") (class "Default")
      (node (ref "R5") (pin "2") (pinfunction "2_2") (pintype "passive"))
      (node (ref "U4") (pin "6") (pinfunction "~{STDBY}_6") (pintype "passive"))
    )
    (net (code "41") (name "Net-(U5-ADDR)") (class "Default")
      (node (ref "R11") (pin "1") (pinfunction "1_1") (pintype "passive"))
      (node (ref "U5") (pin "1") (pinfunction "ADDR_1") (pintype "passive"))
    )
    (net (code "42") (name "Net-(U5-ALERT)") (class "Default")
      (node (ref "R6") (pin "2") (pinfunction "2_2") (pintype "passive"))
      (node (ref "U5") (pin "2") (pinfunction "ALERT_2") (pintype "passive"))
    )
    (net (code "43") (name "Net-(U5-VDD)") (class "Default")
      (node (ref "C7") (pin "1") (pinfunction "1_1") (pintype "passive"))
      (node (ref "C9") (pin "1") (pinfunction "1_1") (pintype "passive"))
      (node (ref "FB1") (pin "1") (pinfunction "1_1") (pintype "passive"))
      (node (ref "U5") (pin "8") (pinfunction "VDD_8") (pintype "passive"))
    )
    (net (code "44") (name "Net-(U7-ADDR)") (class "Default")
      (node (ref "R19") (pin "2") (pinfunction "2_2") (pintype "passive"))
      (node (ref "U7") (pin "1") (pinfunction "ADDR_1") (pintype "passive"))
    )
    (net (code "45") (name "Net-(U7-PWM)") (class "Default")
      (node (ref "R24") (pin "1") (pinfunction "1_1") (pintype "passive"))
      (node (ref "U7") (pin "4") (pinfunction "PWM_4") (pintype "passive"))
      (node (ref "U7") (pin "5") (pinfunction "Sense_5") (pintype "passive"))
    )
    (net (code "46") (name "Net-(U7-P_GND)") (class "Default")
      (node (ref "R17") (pin "2") (pinfunction "2_2") (pintype "passive"))
      (node (ref "U7") (pin "11") (pinfunction "P_GND_11") (pintype "passive"))
    )
    (net (code "47") (name "Net-(U7-nRESET)") (class "Default")
      (node (ref "R18") (pin "2") (pinfunction "2_2") (pintype "passive"))
      (node (ref "U7") (pin "2") (pinfunction "nRESET_2") (pintype "passive"))
    )
    (net (code "48") (name "Net-(U7-nWAKE)") (class "Default")
      (node (ref "R25") (pin "1") (pinfunction "1_1") (pintype "passive"))
      (node (ref "U7") (pin "7") (pinfunction "nWAKE_7") (pintype "passive"))
    )
    (net (code "49") (name "Net-(U8-FB)") (class "Default")
      (node (ref "R27") (pin "1") (pinfunction "1_1") (pintype "passive"))
      (node (ref "R42") (pin "2") (pinfunction "2_2") (pintype "passive"))
      (node (ref "U8") (pin "3") (pinfunction "FB_3") (pintype "passive"))
    )
    (net (code "50") (name "Net-(U9-B)") (class "Default")
      (node (ref "R31") (pin "2") (pinfunction "2_2") (pintype "passive"))
      (node (ref "U9") (pin "3") (pinfunction "B_3") (pintype "passive"))
    )
    (net (code "51") (name "Net-(U9-G)") (class "Default")
      (node (ref "R30") (pin "2") (pinfunction "2_2") (pintype "passive"))
      (node (ref "U9") (pin "4") (pinfunction "G_4") (pintype "passive"))
    )
    (net (code "52") (name "Net-(U9-R)") (class "Default")
      (node (ref "R26") (pin "2") (pinfunction "2_2") (pintype "passive"))
      (node (ref "U9") (pin "1") (pinfunction "R_1") (pintype "passive"))
    )
    (net (code "53") (name "Net-(U10-IO2)") (class "Default")
      (node (ref "R39") (pin "2") (pinfunction "2_2") (pintype "passive"))
      (node (ref "U10") (pin "24") (pinfunction "IO2_24") (pintype "passive"))
    )
    (net (code "54") (name "Net-(U11-X1)") (class "Default")
      (node (ref "C25") (pin "2") (pinfunction "2_2") (pintype "passive"))
      (node (ref "U11") (pin "1") (pinfunction "X1_1") (pintype "passive"))
      (node (ref "X1") (pin "1") (pinfunction "inp_1") (pintype "passive"))
    )
    (net (code "55") (name "Net-(U11-X2)") (class "Default")
      (node (ref "C26") (pin "2") (pinfunction "2_2") (pintype "passive"))
      (node (ref "U11") (pin "2") (pinfunction "X2_2") (pintype "passive"))
      (node (ref "X1") (pin "2") (pinfunction "out_2") (pintype "passive"))
    )
    (net (code "56") (name "VBAT") (class "Default")
      (node (ref "C10") (pin "2") (pinfunction "2_2") (pintype "passive"))
      (node (ref "P1") (pin "1") (pinfunction "1_1") (pintype "passive"))
      (node (ref "Q1") (pin "3") (pinfunction "D_3") (pintype "passive"))
      (node (ref "U4") (pin "5") (pinfunction "BAT_5") (pintype "passive"))
    )
    (net (code "57") (name "unconnected-(U1-D+-Pad3)") (class "Default")
      (node (ref "U1") (pin "3") (pinfunction "D+_3") (pintype "passive+no_connect"))
    )
    (net (code "58") (name "unconnected-(U1-D--Pad2)") (class "Default")
      (node (ref "U1") (pin "2") (pinfunction "D-_2") (pintype "passive+no_connect"))
    )
    (net (code "59") (name "unconnected-(U1-ID-Pad4)") (class "Default")
      (node (ref "U1") (pin "4") (pinfunction "ID_4") (pintype "passive+no_connect"))
    )
    (net (code "60") (name "unconnected-(U5-A1-Pad5)") (class "Default")
      (node (ref "U5") (pin "5") (pinfunction "A1_5") (pintype "passive+no_connect"))
    )
    (net (code "61") (name "unconnected-(U5-A2-Pad6)") (class "Default")
      (node (ref "U5") (pin "6") (pinfunction "A2_6") (pintype "passive+no_connect"))
    )
    (net (code "62") (name "unconnected-(U5-A3-Pad7)") (class "Default")
      (node (ref "U5") (pin "7") (pinfunction "A3_7") (pintype "passive+no_connect"))
    )
    (net (code "63") (name "unconnected-(U7-nINT-Pad3)") (class "Default")
      (node (ref "U7") (pin "3") (pinfunction "nINT_3") (pintype "passive+no_connect"))
    )
    (net (code "64") (name "unconnected-(U8-NC-Pad6)") (class "Default")
      (node (ref "U8") (pin "6") (pinfunction "NC_6") (pintype "passive"))
    )
    (net (code "65") (name "unconnected-(U10-CLK-Pad20)") (class "Default")
      (node (ref "U10") (pin "20") (pinfunction "CLK_20") (pintype "passive+no_connect"))
    )
    (net (code "66") (name "unconnected-(U10-CMD-Pad19)") (class "Default")
      (node (ref "U10") (pin "19") (pinfunction "CMD_19") (pintype "passive+no_connect"))
    )
    (net (code "67") (name "unconnected-(U10-IO4-Pad26)") (class "Default")
      (node (ref "U10") (pin "26") (pinfunction "IO4_26") (pintype "passive+no_connect"))
    )
    (net (code "68") (name "unconnected-(U10-IO5-Pad29)") (class "Default")
      (node (ref "U10") (pin "29") (pinfunction "IO5_29") (pintype "passive+no_connect"))
    )
    (net (code "69") (name "unconnected-(U10-IO12-Pad14)") (class "Default")
      (node (ref "U10") (pin "14") (pinfunction "IO12_14") (pintype "passive+no_connect"))
    )
    (net (code "70") (name "unconnected-(U10-IO13-Pad16)") (class "Default")
      (node (ref "U10") (pin "16") (pinfunction "IO13_16") (pintype "passive+no_connect"))
    )
    (net (code "71") (name "unconnected-(U10-IO15-Pad23)") (class "Default")
      (node (ref "U10") (pin "23") (pinfunction "IO15_23") (pintype "passive+no_connect"))
    )
    (net (code "72") (name "unconnected-(U10-IO19-Pad31)") (class "Default")
      (node (ref "U10") (pin "31") (pinfunction "IO19_31") (pintype "passive+no_connect"))
    )
    (net (code "73") (name "unconnected-(U10-IO23-Pad37)") (class "Default")
      (node (ref "U10") (pin "37") (pinfunction "IO23_37") (pintype "passive+no_connect"))
    )
    (net (code "74") (name "unconnected-(U10-IO25-Pad10)") (class "Default")
      (node (ref "U10") (pin "10") (pinfunction "IO25_10") (pintype "passive+no_connect"))
    )
    (net (code "75") (name "unconnected-(U10-IO26-Pad11)") (class "Default")
      (node (ref "U10") (pin "11") (pinfunction "IO26_11") (pintype "passive+no_connect"))
    )
    (net (code "76") (name "unconnected-(U10-IO27-Pad12)") (class "Default")
      (node (ref "U10") (pin "12") (pinfunction "IO27_12") (pintype "passive+no_connect"))
    )
    (net (code "77") (name "unconnected-(U10-IO33-Pad9)") (class "Default")
      (node (ref "U10") (pin "9") (pinfunction "IO33_9") (pintype "passive+no_connect"))
    )
    (net (code "78") (name "unconnected-(U10-IO35-Pad7)") (class "Default")
      (node (ref "U10") (pin "7") (pinfunction "IO35_7") (pintype "passive+no_connect"))
    )
    (net (code "79") (name "unconnected-(U10-NC-Pad32)") (class "Default")
      (node (ref "U10") (pin "32") (pinfunction "NC_32") (pintype "passive+no_connect"))
    )
    (net (code "80") (name "unconnected-(U10-SD0-Pad21)") (class "Default")
      (node (ref "U10") (pin "21") (pinfunction "SD0_21") (pintype "passive+no_connect"))
    )
    (net (code "81") (name "unconnected-(U10-SD1-Pad22)") (class "Default")
      (node (ref "U10") (pin "22") (pinfunction "SD1_22") (pintype "passive+no_connect"))
    )
    (net (code "82") (name "unconnected-(U10-SD2-Pad17)") (class "Default")
      (node (ref "U10") (pin "17") (pinfunction "SD2_17") (pintype "passive+no_connect"))
    )
    (net (code "83") (name "unconnected-(U10-SD3-Pad18)") (class "Default")
      (node (ref "U10") (pin "18") (pinfunction "SD3_18") (pintype "passive+no_connect"))
    )
    (net (code "84") (name "unconnected-(U10-SENSOR_VN-Pad5)") (class "Default")
      (node (ref "U10") (pin "5") (pinfunction "SENSOR_VN_5") (pintype "passive+no_connect"))
    )
    (net (code "85") (name "unconnected-(U10-SENSOR_VP-Pad4)") (class "Default")
      (node (ref "U10") (pin "4") (pinfunction "SENSOR_VP_4") (pintype "passive+no_connect"))
    )
    (net (code "86") (name "unconnected-(U11-SQW-Pad7)") (class "Default")
      (node (ref "U11") (pin "7") (pinfunction "SQW_7") (pintype "passive+no_connect"))
    )
  )
)
